# AIRZAI_LID_BD_REVB_Sheet1.net
KiCad netlist of a schematic drawn in Altium Designer
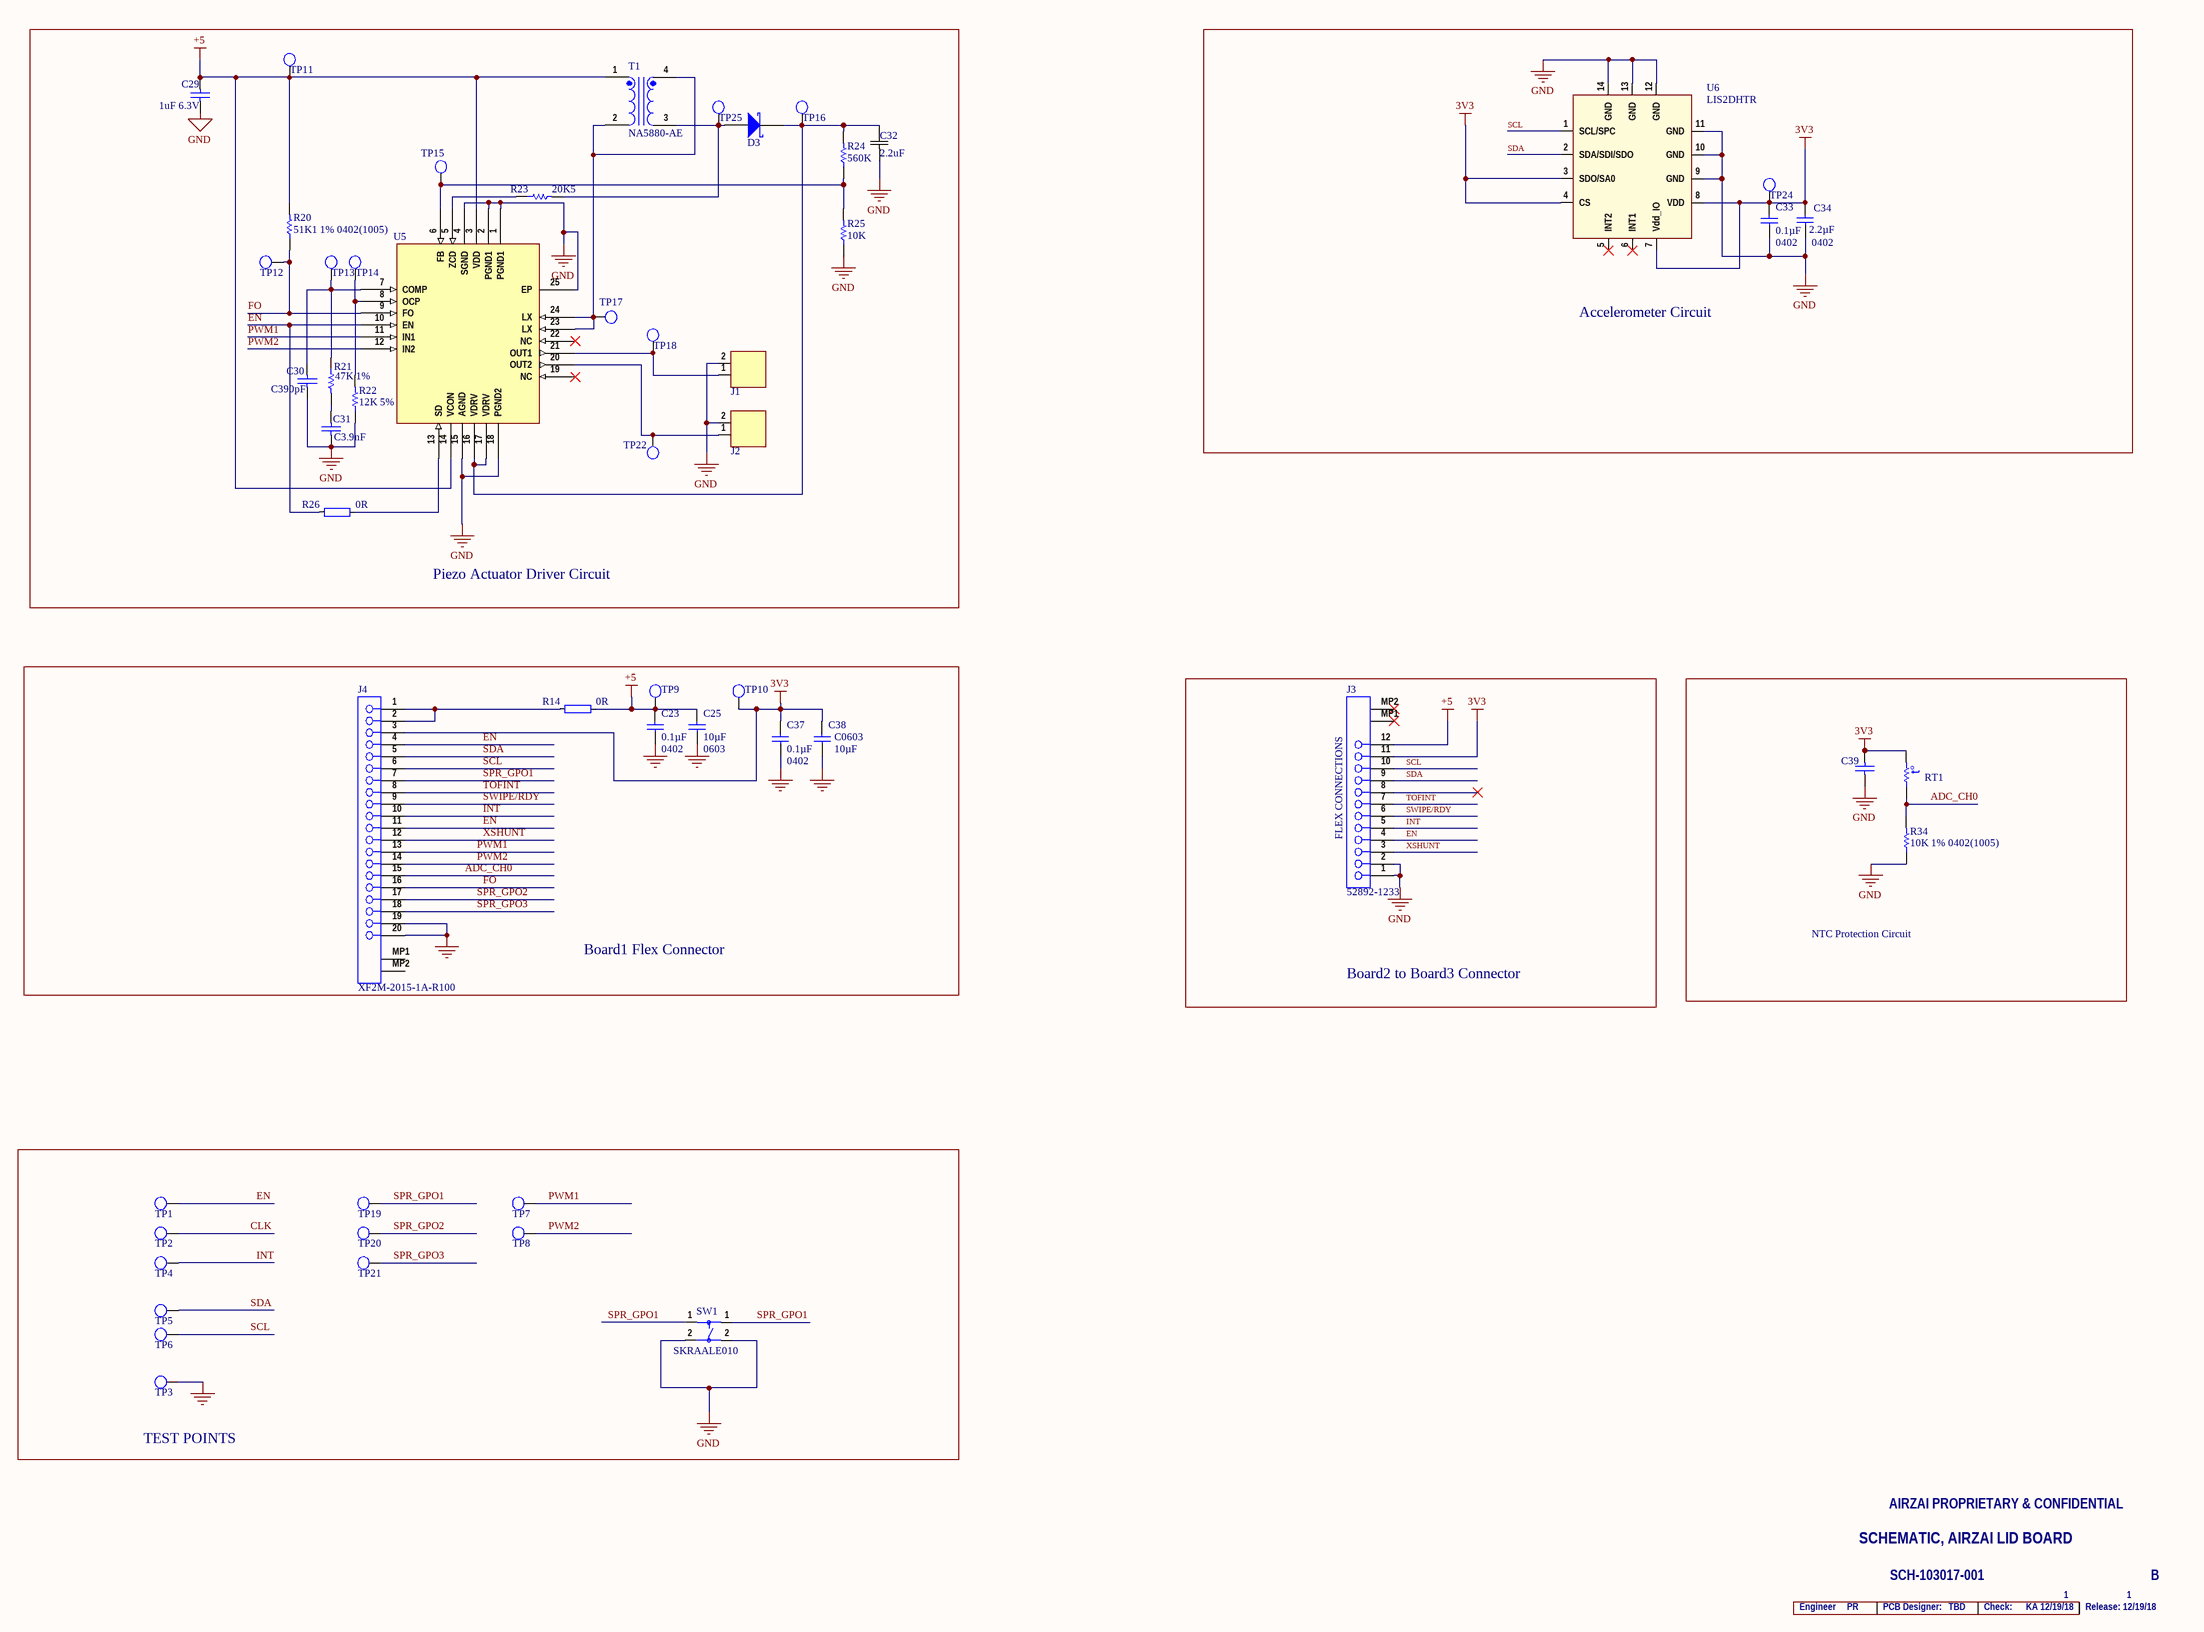
[diagram p0: AIRZAI_LID_BD_REVB Sheet1.SchDoc]

(export (version "E")
  (design (tool "Eeschema 10.0.6"))
  (components
    (comp (ref "C23")
      (value "0.1µF")
      (footprint "0402")
      (description "Capacitor, X7R, ±10%")
      (fields (field (name "MANUFACTURER") "TDK") (field (name "MANUFACTURER PART NUMBER") "C1005X7R1C104K"))
      (libsource (lib "Nordic Passive DB") (part "CAP"))
    )
    (comp (ref "C25")
      (value "10µF")
      (footprint "0603")
      (description "6.3volts X5R 20%")
      (fields
        (field (name "MANUFACTURER") "MURATA")
        (field (name "MANUFACTURER PART NUMBER") "GRM188R60J106ME47D")
      )
      (libsource (lib "Nordic Passive DB") (part "CAP"))
    )
    (comp (ref "C29")
      (value "1uF 6.3V")
      (footprint "CAPC0402(1005)60_M")
      (description "CAP 1uF 6.3V ±10% 0402 (1005 Metric) Thickness 0.6mm SMD")
      (fields (field (name "TOLERANCE") "Â±10%") (field (name "MANUFACTURER") "MURATA"))
      (libsource (lib "AIRZAI_LID_BD_REVA") (part "CAP"))
    )
    (comp (ref "C30")
      (value "C390pF")
      (footprint "CAPC0402(1005)60_M")
      (description "CAP 390pF 50V ±20% 0402 (1005 Metric) Thickness 0.6mm SMD")
      (fields (field (name "TOLERANCE") "Â±20%") (field (name "MANUFACTURER") "KEMET"))
      (libsource (lib "") (part "CAP_1"))
    )
    (comp (ref "C31")
      (value "C3.9nF")
      (footprint "CAPC0402(1005)60_M")
      (description "CAP 3.9nF 50V ±10% 0402 (1005 Metric) Thickness 0.6mm SMD")
      (fields (field (name "TOLERANCE") "Â±10%") (field (name "MANUFACTURER") "TDK"))
      (libsource (lib "AIRZAI_LID_BD_REVA") (part "CAP"))
    )
    (comp (ref "C32")
      (value "2.2uF")
      (footprint "C1210_N")
      (description "Imported")
      (fields
        (field (name "MANUFACTURER_PART_NUMBER") "C3225JB2A225K230AB")
        (field (name "MANUFACTURER") "TDK")
      )
      (libsource (lib "C3225JB2A225K230AB") (part "C3225JB2A225K230"))
    )
    (comp (ref "C33")
      (value "0.1µF")
      (footprint "0402")
      (description "Capacitor, X7R, ±10%")
      (fields (field (name "MANUFACTURER") "TDK") (field (name "MANUFACTURER PART NUMBER") "C1005X7R1C104K"))
      (libsource (lib "Nordic Passive DB") (part "CAP"))
    )
    (comp (ref "C34")
      (value "2.2µF")
      (footprint "0402")
      (description "Capacitor, X7R, ±10%")
      (fields (field (name "MANUFACTURER") "TDK") (field (name "MANUFACTURER PART NUMBER") "C1005X5R0J225M"))
      (libsource (lib "Nordic Passive DB") (part "CAP"))
    )
    (comp (ref "C37")
      (value "0.1µF")
      (footprint "0402")
      (description "Capacitor, X7R, ±10%")
      (fields (field (name "MANUFACTURER") "TDK") (field (name "MANUFACTURER PART NUMBER") "C1005X7R1C104K"))
      (libsource (lib "Nordic Passive DB") (part "CAP"))
    )
    (comp (ref "C38")
      (value "10µF")
      (footprint "C0603")
      (description "Capacitor, X7R, ±10%")
      (fields
        (field (name "MANUFACTURER") "MURATA")
        (field (name "MANUFACTURER PART NUMBER") "GRM188R60J106ME47D")
      )
      (libsource (lib "Nordic Passive DB") (part "CAP"))
    )
    (comp (ref "C39")
      (value "CAP 100nF 10V 0402(1005)")
      (footprint "CAPC0402(1005)60_M")
      (description "CAP 100nF 10V ±10% 0402 (1005 Metric) Thickness 0.6mm SMD")
      (fields (field (name "TOLERANCE") "Â±10%") (field (name "MANUFACTURER") "Yageo"))
      (libsource (lib "AIRZAI_LID_BD_REVA") (part "CAP"))
    )
    (comp (ref "D3")
      (value "STPS2H100A")
      (footprint "STM-SMA-2_V")
      (description "Power Schottky Rectifier, 2 A, 100 V, 2-Pin SMD (SMA), RoHS, Tape and Reel")
      (fields (field (name "MANUFACTURER") "STMicroelectronics"))
      (libsource (lib "AIRZAI_LID_BD_REVA") (part "DSKY-AK-2"))
    )
    (comp (ref "J1")
      (value "~")
      (footprint "CON_78171_0002")
      (fields (field (name "MANUFACTURER PART NUMBER") "781710002") (field (name "MANUFACTURER") "MOLEX"))
      (libsource (lib "DFM_JBKEGSVS_Library") (part "CONN_BM02B_SURS_TF"))
    )
    (comp (ref "J2")
      (value "~")
      (footprint "CON_78171_0002")
      (fields (field (name "MANUFACTURER PART NUMBER") "781710002") (field (name "MANUFACTURER") "MOLEX"))
      (libsource (lib "DFM_JBKEGSVS_Library") (part "CONN_BM02B_SURS_TF"))
    )
    (comp (ref "J3")
      (value "52892-1233")
      (footprint "MOLX-52892-1233")
      (fields (field (name "MANUFACTURER") "MOLEX") (field (name "MANUFACTURER PART NUMBER") "0528921233"))
      (libsource (lib "AIRZAI_LID_BD_REVA") (part "MOLX-52892-1233"))
    )
    (comp (ref "J4")
      (value "XF2M-2015-1A-R100")
      (footprint "Omron_XF2M-2015-1A_0")
      (fields (field (name "MANUFACTURER") "OMRON ELECTRONIC COMPONENTS"))
      (libsource (lib "AIRZAI_LID_BD_REVA") (part "XF2M-2015-1A-R100"))
    )
    (comp (ref "R14")
      (value "0R")
      (footprint "0402")
      (description "Resistor, ±1%, 0.063W")
      (fields
        (field (name "MANUFACTURER") "Panasonic")
        (field (name "MANUFACTURER PART NUMBER") "ERJ-2GE0R00X")
      )
      (libsource (lib "Nordic Passive DB") (part "RES_1"))
    )
    (comp (ref "R20")
      (value "51K1 1% 0402(1005)")
      (footprint "0402")
      (description "51K1 0.063W 1% 0402 (1005 Metric)  SMD")
      (fields (field (name "POWER") "0.063 W") (field (name "TOLERANCE") "1 %"))
      (libsource (lib "") (part "RES_2"))
    )
    (comp (ref "R21")
      (value "47K 1%")
      (footprint "0402")
      (description "47K 0.063W 1% 0402 (1005 Metric)  SMD")
      (fields (field (name "POWER") "0.063 W") (field (name "TOLERANCE") "1 %"))
      (libsource (lib "AIRZAI_LID_BD_REVA") (part "RES"))
    )
    (comp (ref "R22")
      (value "12K 5%")
      (footprint "0402")
      (description "12K 0.063W 5% 0402 (1005 Metric)  SMD")
      (fields (field (name "TOLERANCE") "5 %") (field (name "POWER") "0.063 W"))
      (libsource (lib "") (part "RES_2"))
    )
    (comp (ref "R23")
      (value "20K5")
      (footprint "0402")
      (description "20K5 0.063W 1% 0402 (1005 Metric)  SMD")
      (fields (field (name "POWER") "0.063 W") (field (name "TOLERANCE") "1 %"))
      (libsource (lib "") (part "RES_1"))
    )
    (comp (ref "R24")
      (value "560K")
      (footprint "0402")
      (description "560K 0.063W 1% 0402 (1005 Metric)  SMD")
      (fields (field (name "POWER") "0.063 W") (field (name "TOLERANCE") "1 %"))
      (libsource (lib "") (part "RES_2"))
    )
    (comp (ref "R25")
      (value "10K")
      (footprint "0402")
      (description "10K 0.063W 5% 0402 (1005 Metric)  SMD")
      (fields (field (name "TOLERANCE") "5 %") (field (name "POWER") "0.063 W"))
      (libsource (lib "") (part "RES_2"))
    )
    (comp (ref "R26")
      (value "0R")
      (footprint "0402")
      (description "Resistor, ±1%, 0.063W")
      (fields
        (field (name "MANUFACTURER") "Panasonic")
        (field (name "MANUFACTURER PART NUMBER") "ERJ-2GE0R00X")
      )
      (libsource (lib "Nordic Passive DB") (part "RES_1"))
    )
    (comp (ref "R34")
      (value "10K 1% 0402(1005)")
      (footprint "0402")
      (description "10K 0.063W 1% 0402 (1005 Metric)  SMD")
      (fields (field (name "TOLERANCE") "1 %") (field (name "POWER") "0.063 W"))
      (libsource (lib "") (part "RES_2"))
    )
    (comp (ref "RT1")
      (value "NCP18XH103F03RB")
      (footprint "MURA-NCP18XH103F03RB-2_V")
      (description "NTC Thermistor, 10 KOhm, +/- 1%, 0.1 W, -40 to 125 degC, 0603 (1608 Metric), RoHS, Tape and Reel")
      (fields (field (name "MANUFACTURER") "Murata") (field (name "TOLERANCE") "1 %"))
      (libsource (lib "AIRZAI_LID_BD_REVA") (part "MURA-NCP18XH103F03RB-2"))
    )
    (comp (ref "SW1")
      (value "SKRAALE010")
      (footprint "SW_ALPS_SKRAALE010")
      (fields (field (name "MANUFACTURER") "ALPS") (field (name "MANUFACTURER PART NUMBER") "SKRAAKE010"))
      (libsource (lib "DFM_JBKEGSVS_Library") (part "SW_SKRAALE010"))
    )
    (comp (ref "T1")
      (value "NA5880-AE")
      (footprint "Coilcraft_NA5880-AE_MFG")
      (fields (field (name "MANUFACTURER") "CoilCraft") (field (name "TOLERANCE") "20%"))
      (libsource (lib "AIRZAI_LID_BD_REVA") (part "TRANS-DOT-1-1-4"))
    )
    (comp (ref "TP1")
      (value "TESTPOINT")
      (footprint "TP_0.9MM")
      (libsource (lib "DFM_JBKEGSVS_Library") (part "TESTPOINT"))
    )
    (comp (ref "TP2")
      (value "TESTPOINT")
      (footprint "TP_0.9MM")
      (libsource (lib "DFM_JBKEGSVS_Library") (part "TESTPOINT"))
    )
    (comp (ref "TP3")
      (value "TESTPOINT")
      (footprint "TP_0.9MM")
      (libsource (lib "DFM_JBKEGSVS_Library") (part "TESTPOINT"))
    )
    (comp (ref "TP4")
      (value "TESTPOINT")
      (footprint "TP_0.9MM")
      (libsource (lib "DFM_JBKEGSVS_Library") (part "TESTPOINT"))
    )
    (comp (ref "TP5")
      (value "TESTPOINT")
      (footprint "TP_0.9MM")
      (libsource (lib "DFM_JBKEGSVS_Library") (part "TESTPOINT"))
    )
    (comp (ref "TP6")
      (value "TESTPOINT")
      (footprint "TP_0.9MM")
      (libsource (lib "DFM_JBKEGSVS_Library") (part "TESTPOINT"))
    )
    (comp (ref "TP7")
      (value "TESTPOINT")
      (footprint "TP_0.9MM")
      (libsource (lib "DFM_JBKEGSVS_Library") (part "TESTPOINT"))
    )
    (comp (ref "TP8")
      (value "TESTPOINT")
      (footprint "TP_0.9MM")
      (libsource (lib "DFM_JBKEGSVS_Library") (part "TESTPOINT"))
    )
    (comp (ref "TP9")
      (value "TESTPOINT")
      (footprint "TP_0.9MM")
      (libsource (lib "DFM_JBKEGSVS_Library") (part "TESTPOINT"))
    )
    (comp (ref "TP10")
      (value "TESTPOINT")
      (footprint "TP_0.9MM")
      (libsource (lib "DFM_JBKEGSVS_Library") (part "TESTPOINT"))
    )
    (comp (ref "TP11")
      (value "TESTPOINT")
      (footprint "TP_0.9MM")
      (libsource (lib "AIRZAI_LID_BD_REVA") (part "TESTPOINT"))
    )
    (comp (ref "TP12")
      (value "TESTPOINT")
      (footprint "TP_0.9MM")
      (libsource (lib "AIRZAI_LID_BD_REVA") (part "TESTPOINT"))
    )
    (comp (ref "TP13")
      (value "TESTPOINT")
      (footprint "TP_0.9MM")
      (libsource (lib "AIRZAI_LID_BD_REVA") (part "TESTPOINT"))
    )
    (comp (ref "TP14")
      (value "TESTPOINT")
      (footprint "TP_0.9MM")
      (libsource (lib "AIRZAI_LID_BD_REVA") (part "TESTPOINT"))
    )
    (comp (ref "TP15")
      (value "TESTPOINT")
      (footprint "TP_0.9MM")
      (libsource (lib "AIRZAI_LID_BD_REVA") (part "TESTPOINT"))
    )
    (comp (ref "TP16")
      (value "TESTPOINT")
      (footprint "TP_0.9MM")
      (libsource (lib "AIRZAI_LID_BD_REVA") (part "TESTPOINT"))
    )
    (comp (ref "TP17")
      (value "TESTPOINT")
      (footprint "TP_0.9MM")
      (libsource (lib "AIRZAI_LID_BD_REVA") (part "TESTPOINT"))
    )
    (comp (ref "TP18")
      (value "TESTPOINT")
      (footprint "TP_0.9MM")
      (libsource (lib "AIRZAI_LID_BD_REVA") (part "TESTPOINT"))
    )
    (comp (ref "TP19")
      (value "TESTPOINT")
      (footprint "TP_0.9MM")
      (libsource (lib "DFM_JBKEGSVS_Library") (part "TESTPOINT"))
    )
    (comp (ref "TP20")
      (value "TESTPOINT")
      (footprint "TP_0.9MM")
      (libsource (lib "DFM_JBKEGSVS_Library") (part "TESTPOINT"))
    )
    (comp (ref "TP21")
      (value "TESTPOINT")
      (footprint "TP_0.9MM")
      (libsource (lib "DFM_JBKEGSVS_Library") (part "TESTPOINT"))
    )
    (comp (ref "TP22")
      (value "TESTPOINT")
      (footprint "TP_0.9MM")
      (libsource (lib "AIRZAI_LID_BD_REVA") (part "TESTPOINT"))
    )
    (comp (ref "TP24")
      (value "TESTPOINT")
      (footprint "TP_0.9MM")
      (libsource (lib "AIRZAI_LID_BD_REVA") (part "TESTPOINT"))
    )
    (comp (ref "TP25")
      (value "TESTPOINT")
      (footprint "TP_0.9MM")
      (libsource (lib "AIRZAI_LID_BD_REVA") (part "TESTPOINT"))
    )
    (comp (ref "U5")
      (value "FAN8841MPXCT-ND")
      (footprint "WFQFN-24-FAN8841MPX")
      (description "IC PIEZO ACTUATOR DVR 24MLP")
      (fields
        (field (name "MANUFACTURER") "ON Semiconductor")
        (field (name "MANUFACTURER PART NUMBER") "FAN8841MPX")
      )
      (libsource (lib "AIRZAI_LID_BD_REVA") (part "FAN8841MPXCT-ND"))
    )
    (comp (ref "U6")
      (value "LIS2DHTR")
      (footprint "STM-LGA-14_L")
      (fields (field (name "MANUFACTURER") "ST"))
      (libsource (lib "AIRZAI_LID_BD_REVA") (part "LIS2DH"))
    )
  )
  (nets
    (net (code "1") (name "+5") (class "Default")
      (node (ref "C23") (pin "1") (pinfunction "1_1") (pintype "passive"))
      (node (ref "C25") (pin "1") (pinfunction "1_1") (pintype "passive"))
      (node (ref "C29") (pin "2") (pinfunction "2_2") (pintype "passive"))
      (node (ref "J3") (pin "12") (pinfunction "12_12") (pintype "passive"))
      (node (ref "R14") (pin "1") (pinfunction "1_1") (pintype "passive"))
      (node (ref "R20") (pin "2") (pinfunction "2_2") (pintype "passive"))
      (node (ref "T1") (pin "1") (pinfunction "1_1") (pintype "passive"))
      (node (ref "TP11") (pin "1") (pinfunction "1_1") (pintype "passive"))
      (node (ref "TP9") (pin "1") (pinfunction "1_1") (pintype "passive"))
      (node (ref "U5") (pin "14") (pinfunction "VCON_14") (pintype "power_in"))
      (node (ref "U5") (pin "3") (pinfunction "VDD_3") (pintype "power_in"))
    )
    (net (code "2") (name "/ADC_CH0") (class "Default")
      (node (ref "J4") (pin "15") (pinfunction "15_15") (pintype "passive"))
      (node (ref "R34") (pin "2") (pinfunction "2_2") (pintype "passive"))
      (node (ref "RT1") (pin "1") (pinfunction "1_1") (pintype "passive"))
    )
    (net (code "3") (name "/CLK") (class "Default")
      (node (ref "TP2") (pin "1") (pinfunction "1_1") (pintype "passive"))
    )
    (net (code "4") (name "/EN") (class "Default")
      (node (ref "J3") (pin "4") (pinfunction "4_4") (pintype "passive"))
      (node (ref "J4") (pin "11") (pinfunction "11_11") (pintype "passive"))
      (node (ref "J4") (pin "4") (pinfunction "4_4") (pintype "passive"))
      (node (ref "R26") (pin "2") (pinfunction "2_2") (pintype "passive"))
      (node (ref "TP1") (pin "1") (pinfunction "1_1") (pintype "passive"))
      (node (ref "U5") (pin "10") (pinfunction "EN_10") (pintype "input"))
    )
    (net (code "5") (name "/FO") (class "Default")
      (node (ref "J4") (pin "16") (pinfunction "16_16") (pintype "passive"))
      (node (ref "R20") (pin "1") (pinfunction "1_1") (pintype "passive"))
      (node (ref "TP12") (pin "1") (pinfunction "1_1") (pintype "passive"))
      (node (ref "U5") (pin "9") (pinfunction "FO_9") (pintype "input"))
    )
    (net (code "6") (name "/INT") (class "Default")
      (node (ref "J3") (pin "5") (pinfunction "5_5") (pintype "passive"))
      (node (ref "J4") (pin "10") (pinfunction "10_10") (pintype "passive"))
      (node (ref "TP4") (pin "1") (pinfunction "1_1") (pintype "passive"))
    )
    (net (code "7") (name "/PWM1") (class "Default")
      (node (ref "J4") (pin "13") (pinfunction "13_13") (pintype "passive"))
      (node (ref "TP7") (pin "1") (pinfunction "1_1") (pintype "passive"))
      (node (ref "U5") (pin "11") (pinfunction "IN1_11") (pintype "input"))
    )
    (net (code "8") (name "/PWM2") (class "Default")
      (node (ref "J4") (pin "14") (pinfunction "14_14") (pintype "passive"))
      (node (ref "TP8") (pin "1") (pinfunction "1_1") (pintype "passive"))
      (node (ref "U5") (pin "12") (pinfunction "IN2_12") (pintype "input"))
    )
    (net (code "9") (name "/SCL") (class "Default")
      (node (ref "J3") (pin "10") (pinfunction "10_10") (pintype "passive"))
      (node (ref "J4") (pin "6") (pinfunction "6_6") (pintype "passive"))
      (node (ref "TP6") (pin "1") (pinfunction "1_1") (pintype "passive"))
      (node (ref "U6") (pin "1") (pinfunction "SCL/SPC_1") (pintype "passive"))
    )
    (net (code "10") (name "/SDA") (class "Default")
      (node (ref "J3") (pin "9") (pinfunction "9_9") (pintype "passive"))
      (node (ref "J4") (pin "5") (pinfunction "5_5") (pintype "passive"))
      (node (ref "TP5") (pin "1") (pinfunction "1_1") (pintype "passive"))
      (node (ref "U6") (pin "2") (pinfunction "SDA/SDI/SDO_2") (pintype "passive"))
    )
    (net (code "11") (name "/SPR_GPO1") (class "Default")
      (node (ref "J4") (pin "7") (pinfunction "7_7") (pintype "passive"))
      (node (ref "SW1") (pin "1") (pinfunction "1_1") (pintype "passive"))
      (node (ref "TP19") (pin "1") (pinfunction "1_1") (pintype "passive"))
    )
    (net (code "12") (name "/SPR_GPO2") (class "Default")
      (node (ref "J4") (pin "17") (pinfunction "17_17") (pintype "passive"))
      (node (ref "TP20") (pin "1") (pinfunction "1_1") (pintype "passive"))
    )
    (net (code "13") (name "/SPR_GPO3") (class "Default")
      (node (ref "J4") (pin "18") (pinfunction "18_18") (pintype "passive"))
      (node (ref "TP21") (pin "1") (pinfunction "1_1") (pintype "passive"))
    )
    (net (code "14") (name "/SWIPE{slash}RDY") (class "Default")
      (node (ref "J3") (pin "6") (pinfunction "6_6") (pintype "passive"))
      (node (ref "J4") (pin "9") (pinfunction "9_9") (pintype "passive"))
    )
    (net (code "15") (name "/TOFINT") (class "Default")
      (node (ref "J3") (pin "7") (pinfunction "7_7") (pintype "passive"))
      (node (ref "J4") (pin "8") (pinfunction "8_8") (pintype "passive"))
    )
    (net (code "16") (name "/XSHUNT") (class "Default")
      (node (ref "J3") (pin "3") (pinfunction "3_3") (pintype "passive"))
      (node (ref "J4") (pin "12") (pinfunction "12_12") (pintype "passive"))
    )
    (net (code "17") (name "3V3") (class "Default")
      (node (ref "C33") (pin "1") (pinfunction "1_1") (pintype "passive"))
      (node (ref "C34") (pin "2") (pinfunction "2_2") (pintype "passive"))
      (node (ref "C37") (pin "1") (pinfunction "1_1") (pintype "passive"))
      (node (ref "C38") (pin "1") (pinfunction "1_1") (pintype "passive"))
      (node (ref "C39") (pin "2") (pinfunction "2_2") (pintype "passive"))
      (node (ref "J3") (pin "11") (pinfunction "11_11") (pintype "passive"))
      (node (ref "J4") (pin "3") (pinfunction "3_3") (pintype "passive"))
      (node (ref "RT1") (pin "2") (pinfunction "2_2") (pintype "passive"))
      (node (ref "TP10") (pin "1") (pinfunction "1_1") (pintype "passive"))
      (node (ref "TP24") (pin "1") (pinfunction "1_1") (pintype "passive"))
      (node (ref "U6") (pin "3") (pinfunction "SDO/SA0_3") (pintype "passive"))
      (node (ref "U6") (pin "4") (pinfunction "CS_4") (pintype "passive"))
      (node (ref "U6") (pin "7") (pinfunction "Vdd_IO_7") (pintype "passive"))
      (node (ref "U6") (pin "8") (pinfunction "VDD_8") (pintype "passive"))
    )
    (net (code "18") (name "GND") (class "Default")
      (node (ref "C23") (pin "2") (pinfunction "2_2") (pintype "passive"))
      (node (ref "C25") (pin "2") (pinfunction "2_2") (pintype "passive"))
      (node (ref "C29") (pin "1") (pinfunction "1_1") (pintype "passive"))
      (node (ref "C30") (pin "2") (pinfunction "2_2") (pintype "passive"))
      (node (ref "C31") (pin "1") (pinfunction "1_1") (pintype "passive"))
      (node (ref "C32") (pin "1") (pinfunction "1_1") (pintype "passive"))
      (node (ref "C33") (pin "2") (pinfunction "2_2") (pintype "passive"))
      (node (ref "C34") (pin "1") (pinfunction "1_1") (pintype "passive"))
      (node (ref "C37") (pin "2") (pinfunction "2_2") (pintype "passive"))
      (node (ref "C38") (pin "2") (pinfunction "2_2") (pintype "passive"))
      (node (ref "C39") (pin "1") (pinfunction "1_1") (pintype "passive"))
      (node (ref "J1") (pin "2") (pinfunction "2_2") (pintype "passive"))
      (node (ref "J2") (pin "2") (pinfunction "2_2") (pintype "passive"))
      (node (ref "J3") (pin "1") (pinfunction "1_1") (pintype "passive"))
      (node (ref "J3") (pin "2") (pinfunction "2_2") (pintype "passive"))
      (node (ref "J4") (pin "19") (pinfunction "19_19") (pintype "passive"))
      (node (ref "J4") (pin "20") (pinfunction "20_20") (pintype "passive"))
      (node (ref "R22") (pin "1") (pinfunction "1_1") (pintype "passive"))
      (node (ref "R25") (pin "1") (pinfunction "1_1") (pintype "passive"))
      (node (ref "R34") (pin "1") (pinfunction "1_1") (pintype "passive"))
      (node (ref "SW1") (pin "2") (pinfunction "2_2") (pintype "passive"))
      (node (ref "TP3") (pin "1") (pinfunction "1_1") (pintype "passive"))
      (node (ref "U5") (pin "1") (pinfunction "PGND1_1") (pintype "power_in"))
      (node (ref "U5") (pin "15") (pinfunction "AGND_15") (pintype "power_in"))
      (node (ref "U5") (pin "18") (pinfunction "PGND2_18") (pintype "power_in"))
      (node (ref "U5") (pin "2") (pinfunction "PGND1_2") (pintype "power_in"))
      (node (ref "U5") (pin "25") (pinfunction "EP_25") (pintype "passive"))
      (node (ref "U5") (pin "4") (pinfunction "SGND_4") (pintype "power_in"))
      (node (ref "U6") (pin "10") (pinfunction "GND_10") (pintype "passive"))
      (node (ref "U6") (pin "11") (pinfunction "GND_11") (pintype "passive"))
      (node (ref "U6") (pin "12") (pinfunction "GND_12") (pintype "passive"))
      (node (ref "U6") (pin "13") (pinfunction "GND_13") (pintype "passive"))
      (node (ref "U6") (pin "14") (pinfunction "GND_14") (pintype "passive"))
      (node (ref "U6") (pin "9") (pinfunction "GND_9") (pintype "passive"))
    )
    (net (code "19") (name "Net-(C31-Pad2)") (class "Default")
      (node (ref "C31") (pin "2") (pinfunction "2_2") (pintype "passive"))
      (node (ref "R21") (pin "2") (pinfunction "2_2") (pintype "passive"))
    )
    (net (code "20") (name "Net-(D3-A)") (class "Default")
      (node (ref "D3") (pin "1") (pinfunction "A_1") (pintype "passive"))
      (node (ref "R23") (pin "2") (pinfunction "2_2") (pintype "passive"))
      (node (ref "T1") (pin "3") (pinfunction "3_3") (pintype "passive"))
      (node (ref "TP25") (pin "1") (pinfunction "1_1") (pintype "passive"))
    )
    (net (code "21") (name "Net-(D3-K)") (class "Default")
      (node (ref "C32") (pin "2") (pinfunction "2_2") (pintype "passive"))
      (node (ref "D3") (pin "2") (pinfunction "K_2") (pintype "passive"))
      (node (ref "R24") (pin "2") (pinfunction "2_2") (pintype "passive"))
      (node (ref "TP16") (pin "1") (pinfunction "1_1") (pintype "passive"))
      (node (ref "U5") (pin "16") (pinfunction "VDRV_16") (pintype "power_in"))
      (node (ref "U5") (pin "17") (pinfunction "VDRV_17") (pintype "power_in"))
    )
    (net (code "22") (name "Net-(J4-Pad1)") (class "Default")
      (node (ref "J4") (pin "1") (pinfunction "1_1") (pintype "passive"))
      (node (ref "J4") (pin "2") (pinfunction "2_2") (pintype "passive"))
      (node (ref "R14") (pin "2") (pinfunction "2_2") (pintype "passive"))
    )
    (net (code "23") (name "Net-(T1-Pad2)") (class "Default")
      (node (ref "T1") (pin "2") (pinfunction "2_2") (pintype "passive"))
      (node (ref "T1") (pin "4") (pinfunction "4_4") (pintype "passive"))
      (node (ref "TP17") (pin "1") (pinfunction "1_1") (pintype "passive"))
      (node (ref "U5") (pin "23") (pinfunction "LX_23") (pintype "input"))
      (node (ref "U5") (pin "24") (pinfunction "LX_24") (pintype "input"))
    )
    (net (code "24") (name "Net-(U5-COMP)") (class "Default")
      (node (ref "C30") (pin "1") (pinfunction "1_1") (pintype "passive"))
      (node (ref "R21") (pin "1") (pinfunction "1_1") (pintype "passive"))
      (node (ref "TP13") (pin "1") (pinfunction "1_1") (pintype "passive"))
      (node (ref "U5") (pin "7") (pinfunction "COMP_7") (pintype "input"))
    )
    (net (code "25") (name "Net-(U5-FB)") (class "Default")
      (node (ref "R24") (pin "1") (pinfunction "1_1") (pintype "passive"))
      (node (ref "R25") (pin "2") (pinfunction "2_2") (pintype "passive"))
      (node (ref "TP15") (pin "1") (pinfunction "1_1") (pintype "passive"))
      (node (ref "U5") (pin "6") (pinfunction "FB_6") (pintype "input"))
    )
    (net (code "26") (name "Net-(U5-OCP)") (class "Default")
      (node (ref "R22") (pin "2") (pinfunction "2_2") (pintype "passive"))
      (node (ref "TP14") (pin "1") (pinfunction "1_1") (pintype "passive"))
      (node (ref "U5") (pin "8") (pinfunction "OCP_8") (pintype "input"))
    )
    (net (code "27") (name "Net-(U5-OUT1)") (class "Default")
      (node (ref "J1") (pin "1") (pinfunction "1_1") (pintype "passive"))
      (node (ref "TP18") (pin "1") (pinfunction "1_1") (pintype "passive"))
      (node (ref "U5") (pin "21") (pinfunction "OUT1_21") (pintype "output"))
    )
    (net (code "28") (name "Net-(U5-OUT2)") (class "Default")
      (node (ref "J2") (pin "1") (pinfunction "1_1") (pintype "passive"))
      (node (ref "TP22") (pin "1") (pinfunction "1_1") (pintype "passive"))
      (node (ref "U5") (pin "20") (pinfunction "OUT2_20") (pintype "output"))
    )
    (net (code "29") (name "Net-(U5-SD)") (class "Default")
      (node (ref "R26") (pin "1") (pinfunction "1_1") (pintype "passive"))
      (node (ref "U5") (pin "13") (pinfunction "SD_13") (pintype "input"))
    )
    (net (code "30") (name "Net-(U5-ZCD)") (class "Default")
      (node (ref "R23") (pin "1") (pinfunction "1_1") (pintype "passive"))
      (node (ref "U5") (pin "5") (pinfunction "ZCD_5") (pintype "input"))
    )
    (net (code "31") (name "unconnected-(J3-Pad8)") (class "Default")
      (node (ref "J3") (pin "8") (pinfunction "8_8") (pintype "passive+no_connect"))
    )
    (net (code "32") (name "unconnected-(J3-PadMP1)") (class "Default")
      (node (ref "J3") (pin "MP1") (pinfunction "MP1_MP1") (pintype "passive+no_connect"))
    )
    (net (code "33") (name "unconnected-(J3-PadMP2)") (class "Default")
      (node (ref "J3") (pin "MP2") (pinfunction "MP2_MP2") (pintype "passive+no_connect"))
    )
    (net (code "34") (name "unconnected-(J4-PadMP1)") (class "Default")
      (node (ref "J4") (pin "MP1") (pinfunction "MP1_MP1") (pintype "passive"))
    )
    (net (code "35") (name "unconnected-(J4-PadMP2)") (class "Default")
      (node (ref "J4") (pin "MP2") (pinfunction "MP2_MP2") (pintype "passive"))
    )
    (net (code "36") (name "unconnected-(U5-NC-Pad19)") (class "Default")
      (node (ref "U5") (pin "19") (pinfunction "NC_19") (pintype "input+no_connect"))
    )
    (net (code "37") (name "unconnected-(U5-NC-Pad22)") (class "Default")
      (node (ref "U5") (pin "22") (pinfunction "NC_22") (pintype "input+no_connect"))
    )
    (net (code "38") (name "unconnected-(U6-INT1-Pad6)") (class "Default")
      (node (ref "U6") (pin "6") (pinfunction "INT1_6") (pintype "passive+no_connect"))
    )
    (net (code "39") (name "unconnected-(U6-INT2-Pad5)") (class "Default")
      (node (ref "U6") (pin "5") (pinfunction "INT2_5") (pintype "passive+no_connect"))
    )
  )
)
